# Audio.net
KiCad netlist of a schematic drawn in Altium Designer
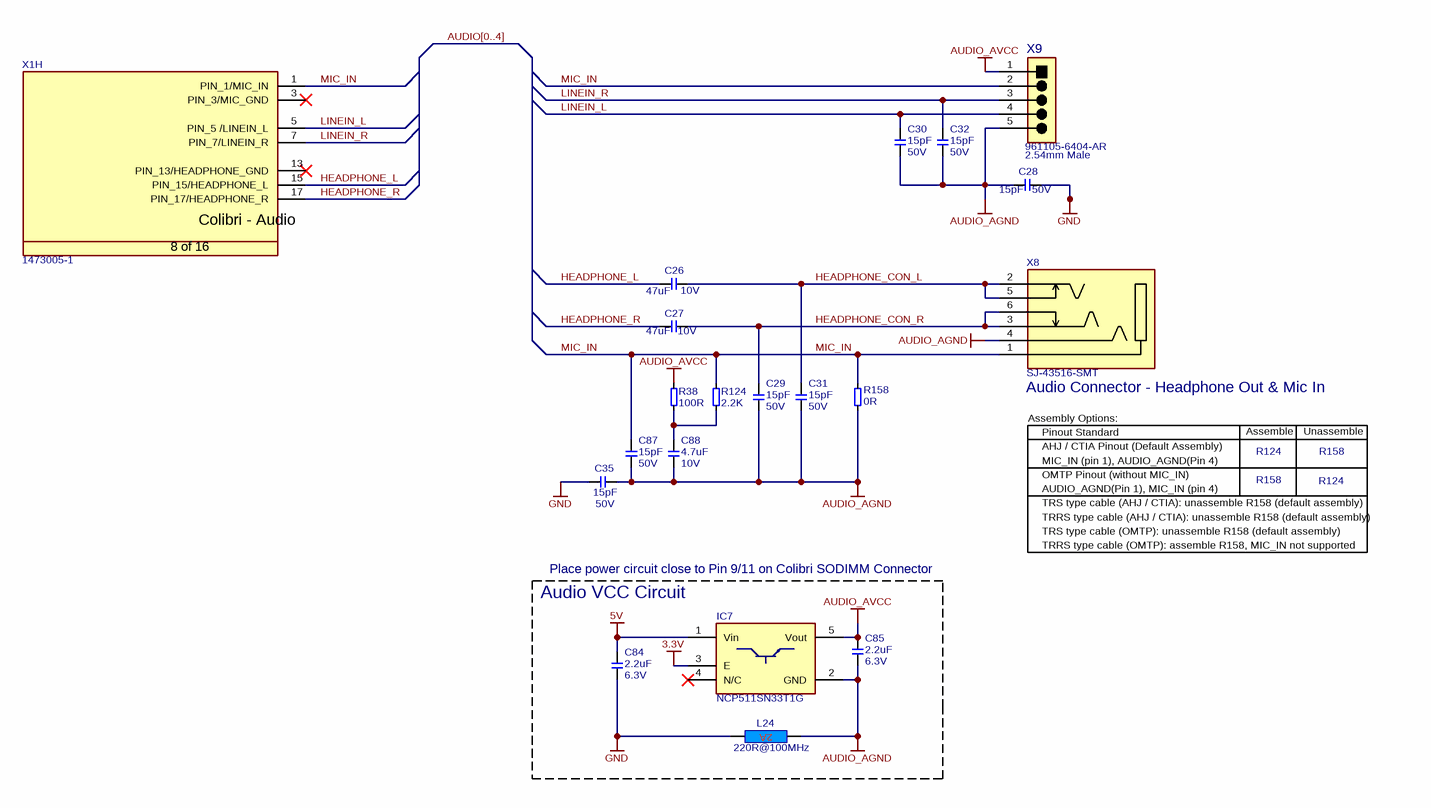
[diagram p0: Audio.SchDoc]

(export (version "E")
  (design (tool "Eeschema 10.0.6"))
  (components
    (comp (ref "C26")
      (value "47uF")
      (footprint "T_CAPC0805X125N")
      (description "Capacitor Ceramic X5R 47uF 10V 20% 0805")
      (fields (field (name "TOLERANCE") "20%") (field (name "RATING") "10V"))
      (libsource (lib "Iris") (part "C-X5R-47uF-10V-20%-0805"))
    )
    (comp (ref "C27")
      (value "47uF")
      (footprint "T_CAPC0805X125N")
      (description "Capacitor Ceramic X5R 47uF 10V 20% 0805")
      (fields (field (name "TOLERANCE") "20%") (field (name "RATING") "10V"))
      (libsource (lib "Iris") (part "C-X5R-47uF-10V-20%-0805"))
    )
    (comp (ref "C28")
      (value "15pF")
      (footprint "CAPC1005X60N")
      (description "Capacitor Ceramic NPO 15pF 50V 5% 0402")
      (fields (field (name "TOLERANCE") "5%") (field (name "RATING") "50V"))
      (libsource (lib "Iris") (part "C-NPO-15pF-50V-5%-0402"))
    )
    (comp (ref "C29")
      (value "15pF")
      (footprint "CAPC1005X60N")
      (description "Capacitor Ceramic NPO 15pF 50V 5% 0402")
      (fields (field (name "TOLERANCE") "5%") (field (name "RATING") "50V"))
      (libsource (lib "Iris") (part "C-NPO-15pF-50V-5%-0402"))
    )
    (comp (ref "C30")
      (value "15pF")
      (footprint "CAPC1005X60N")
      (description "Capacitor Ceramic NPO 15pF 50V 5% 0402")
      (fields (field (name "TOLERANCE") "5%") (field (name "RATING") "50V"))
      (libsource (lib "Iris") (part "C-NPO-15pF-50V-5%-0402"))
    )
    (comp (ref "C31")
      (value "15pF")
      (footprint "CAPC1005X60N")
      (description "Capacitor Ceramic NPO 15pF 50V 5% 0402")
      (fields (field (name "TOLERANCE") "5%") (field (name "RATING") "50V"))
      (libsource (lib "Iris") (part "C-NPO-15pF-50V-5%-0402"))
    )
    (comp (ref "C32")
      (value "15pF")
      (footprint "CAPC1005X60N")
      (description "Capacitor Ceramic NPO 15pF 50V 5% 0402")
      (fields (field (name "TOLERANCE") "5%") (field (name "RATING") "50V"))
      (libsource (lib "Iris") (part "C-NPO-15pF-50V-5%-0402"))
    )
    (comp (ref "C35")
      (value "15pF")
      (footprint "CAPC1005X60N")
      (description "Capacitor Ceramic NPO 15pF 50V 5% 0402")
      (fields (field (name "TOLERANCE") "5%") (field (name "RATING") "50V"))
      (libsource (lib "Iris") (part "C-NPO-15pF-50V-5%-0402"))
    )
    (comp (ref "C84")
      (value "2.2uF")
      (footprint "T_CAPC0603X33N")
      (description "Capacitor Ceramic X5R 2.2uF 6.3V 20% 0603")
      (fields (field (name "TOLERANCE") "20%") (field (name "RATING") "6.3V"))
      (libsource (lib "Iris") (part "C-X5R-2.2uF-6.3V-20%-0603"))
    )
    (comp (ref "C85")
      (value "2.2uF")
      (footprint "T_CAPC0603X33N")
      (description "Capacitor Ceramic X5R 2.2uF 6.3V 20% 0603")
      (fields (field (name "TOLERANCE") "20%") (field (name "RATING") "6.3V"))
      (libsource (lib "Iris") (part "C-X5R-2.2uF-6.3V-20%-0603"))
    )
    (comp (ref "C87")
      (value "15pF")
      (footprint "CAPC1005X60N")
      (description "Capacitor Ceramic NPO 15pF 50V 5% 0402")
      (fields (field (name "TOLERANCE") "5%") (field (name "RATING") "50V"))
      (libsource (lib "Iris") (part "C-NPO-15pF-50V-5%-0402"))
    )
    (comp (ref "C88")
      (value "4.7uF")
      (footprint "T_CAPC0603X33N")
      (description "Capacitor Ceramic X5R 4.7uF 10V 10% 0603")
      (fields (field (name "TOLERANCE") "10%") (field (name "RATING") "10V"))
      (libsource (lib "Iris") (part "C-X5R-4.7uF-10V-10%-0603"))
    )
    (comp (ref "IC7")
      (value "NCP511SN33T1G")
      (footprint "SOT95P279X142-5N")
      (description "NCP511SN33T1G LDO Regulator")
      (fields (field (name "MANUFACTURER PART NO.") "NCP511SN33T1G"))
      (libsource (lib "Iris") (part "IC-ON-NCP511SN33T1G"))
    )
    (comp (ref "L24")
      (value "220R@100MHz")
      (footprint "INDC1608X95N")
      (description "220R@100MHz 2A EMI FILTER")
      (fields (field (name "TOLERANCE") "25%"))
      (libsource (lib "Iris") (part "L-220R@100MHz-2A-25%-0603"))
    )
    (comp (ref "R38")
      (value "100R")
      (footprint "T_RESC0603X30N")
      (description "Resistor 100 ohm 63mW 5% 0603")
      (fields (field (name "TOLERANCE") "5%"))
      (libsource (lib "Iris") (part "R-100R-63mW-5%-0603"))
    )
    (comp (ref "R124")
      (value "2.2K")
      (footprint "RESC1005X40N")
      (description "Resistor 2.2 Kohm 63mW 5% 0402")
      (fields (field (name "TOLERANCE") "5%"))
      (libsource (lib "Iris") (part "R-2.2KR-63mW-5%-0402"))
    )
    (comp (ref "R158")
      (value "0R")
      (footprint "T_RESC0603X30N")
      (description "Resistor 0 ohm 63mW 5% 0603")
      (fields (field (name "TOLERANCE") "5%"))
      (libsource (lib "Iris") (part "R-0R-63mW-5%-0603"))
    )
    (comp (ref "X1")
      (value "1473005-1")
      (footprint "T_Tyco_1473005-1")
      (description "SODIMM Connector")
      (fields (field (name "MANUFACTURER PART NO.") "1473005-1"))
      (libsource (lib "Iris") (part "CON-Tyco-1473005-1-200-0.6mm"))
    )
    (comp (ref "X8")
      (value "SJ-43516-SMT")
      (footprint "T_CI_SJ-43516-SMT")
      (description "3.5mm Stereo Jack SMD with Detect Contact")
      (fields (field (name "MANUFACTURER PART NO.") "SJ-43516-SMT"))
      (libsource (lib "Iris") (part "CON-Cui-SJ-43516-SMT-6-3.5mm"))
    )
    (comp (ref "X9")
      (value "961105-6404-AR")
      (footprint "T_3M_961105-6404-AR")
      (description "Audio Header 5 pins 2.54mm")
      (fields (field (name "MANUFACTURER PART NO.") "961105-6404-AR"))
      (libsource (lib "Iris") (part "CON-3M-961105-6404-AR"))
    )
  )
  (nets
    (net (code "7") (name "/HEADPHONE_CON_L") (class "Default")
      (node (ref "C26") (pin "2") (pinfunction "2_2") (pintype "passive"))
      (node (ref "C31") (pin "2") (pinfunction "2_2") (pintype "passive"))
      (node (ref "X8") (pin "2") (pinfunction "2_2") (pintype "passive"))
      (node (ref "X8") (pin "5") (pinfunction "5_5") (pintype "passive"))
    )
    (net (code "8") (name "/HEADPHONE_CON_R") (class "Default")
      (node (ref "C27") (pin "2") (pinfunction "2_2") (pintype "passive"))
      (node (ref "C29") (pin "2") (pinfunction "2_2") (pintype "passive"))
      (node (ref "X8") (pin "3") (pinfunction "3_3") (pintype "passive"))
      (node (ref "X8") (pin "6") (pinfunction "6_6") (pintype "passive"))
    )
    (net (code "9") (name "/HEADPHONE_L") (class "Default")
      (node (ref "C26") (pin "1") (pinfunction "1_1") (pintype "passive"))
      (node (ref "X1") (pin "15") (pinfunction "PIN_15/HEADPHONE_L_15") (pintype "passive"))
    )
    (net (code "10") (name "/HEADPHONE_R") (class "Default")
      (node (ref "C27") (pin "1") (pinfunction "1_1") (pintype "passive"))
      (node (ref "X1") (pin "17") (pinfunction "PIN_17/HEADPHONE_R_17") (pintype "passive"))
    )
    (net (code "11") (name "/LINEIN_L") (class "Default")
      (node (ref "C30") (pin "2") (pinfunction "2_2") (pintype "passive"))
      (node (ref "X1") (pin "5") (pinfunction "PIN_5_/LINEIN_L_5") (pintype "passive"))
      (node (ref "X9") (pin "4") (pintype "passive"))
    )
    (net (code "12") (name "/LINEIN_R") (class "Default")
      (node (ref "C32") (pin "2") (pinfunction "2_2") (pintype "passive"))
      (node (ref "X1") (pin "7") (pinfunction "PIN_7/LINEIN_R_7") (pintype "passive"))
      (node (ref "X9") (pin "3") (pintype "passive"))
    )
    (net (code "13") (name "/MIC_IN") (class "Default")
      (node (ref "C87") (pin "2") (pinfunction "2_2") (pintype "passive"))
      (node (ref "R124") (pin "2") (pinfunction "2_2") (pintype "passive"))
      (node (ref "R158") (pin "1") (pinfunction "1_1") (pintype "passive"))
      (node (ref "X1") (pin "1") (pinfunction "PIN_1/MIC_IN_1") (pintype "passive"))
      (node (ref "X8") (pin "1") (pinfunction "1_1") (pintype "passive"))
      (node (ref "X9") (pin "2") (pintype "passive"))
    )
    (net (code "14") (name "3.3V") (class "Default")
      (node (ref "IC7") (pin "3") (pinfunction "E_3") (pintype "passive"))
    )
    (net (code "15") (name "5V") (class "Default")
      (node (ref "C84") (pin "2") (pinfunction "2_2") (pintype "passive"))
      (node (ref "IC7") (pin "1") (pinfunction "Vin_1") (pintype "passive"))
    )
    (net (code "16") (name "AUDIO_AGND") (class "Default")
      (node (ref "C28") (pin "1") (pinfunction "1_1") (pintype "passive"))
      (node (ref "C29") (pin "1") (pinfunction "1_1") (pintype "passive"))
      (node (ref "C30") (pin "1") (pinfunction "1_1") (pintype "passive"))
      (node (ref "C31") (pin "1") (pinfunction "1_1") (pintype "passive"))
      (node (ref "C32") (pin "1") (pinfunction "1_1") (pintype "passive"))
      (node (ref "C35") (pin "2") (pinfunction "2_2") (pintype "passive"))
      (node (ref "C85") (pin "1") (pinfunction "1_1") (pintype "passive"))
      (node (ref "C87") (pin "1") (pinfunction "1_1") (pintype "passive"))
      (node (ref "C88") (pin "1") (pinfunction "1_1") (pintype "passive"))
      (node (ref "IC7") (pin "2") (pinfunction "GND_2") (pintype "passive"))
      (node (ref "L24") (pin "1") (pinfunction "1_1") (pintype "passive"))
      (node (ref "R158") (pin "2") (pinfunction "2_2") (pintype "passive"))
      (node (ref "X8") (pin "4") (pinfunction "4_4") (pintype "passive"))
      (node (ref "X9") (pin "5") (pintype "passive"))
    )
    (net (code "17") (name "AUDIO_AVCC") (class "Default")
      (node (ref "C85") (pin "2") (pinfunction "2_2") (pintype "passive"))
      (node (ref "IC7") (pin "5") (pinfunction "Vout_5") (pintype "passive"))
      (node (ref "R38") (pin "1") (pinfunction "1_1") (pintype "passive"))
      (node (ref "X9") (pin "1") (pintype "passive"))
    )
    (net (code "18") (name "GND") (class "Default")
      (node (ref "C28") (pin "2") (pinfunction "2_2") (pintype "passive"))
      (node (ref "C35") (pin "1") (pinfunction "1_1") (pintype "passive"))
      (node (ref "C84") (pin "1") (pinfunction "1_1") (pintype "passive"))
      (node (ref "L24") (pin "2") (pinfunction "2_2") (pintype "passive"))
    )
    (net (code "19") (name "Net-(C88-Pad2)") (class "Default")
      (node (ref "C88") (pin "2") (pinfunction "2_2") (pintype "passive"))
      (node (ref "R124") (pin "1") (pinfunction "1_1") (pintype "passive"))
      (node (ref "R38") (pin "2") (pinfunction "2_2") (pintype "passive"))
    )
    (net (code "20") (name "unconnected-(IC7-N{slash}C-Pad4)") (class "Default")
      (node (ref "IC7") (pin "4") (pinfunction "N/C_4") (pintype "passive+no_connect"))
    )
    (net (code "21") (name "unconnected-(X1H-PIN_3{slash}MIC_GND-Pad3)") (class "Default")
      (node (ref "X1") (pin "3") (pinfunction "PIN_3/MIC_GND_3") (pintype "passive+no_connect"))
    )
    (net (code "22") (name "unconnected-(X1H-PIN_13{slash}HEADPHONE_GND-Pad13)") (class "Default")
      (node (ref "X1") (pin "13") (pinfunction "PIN_13/HEADPHONE_GND_13") (pintype "passive+no_connect"))
    )
  )
)
